# KUBODriver_Driver.net
KiCad netlist of a schematic drawn in Altium Designer
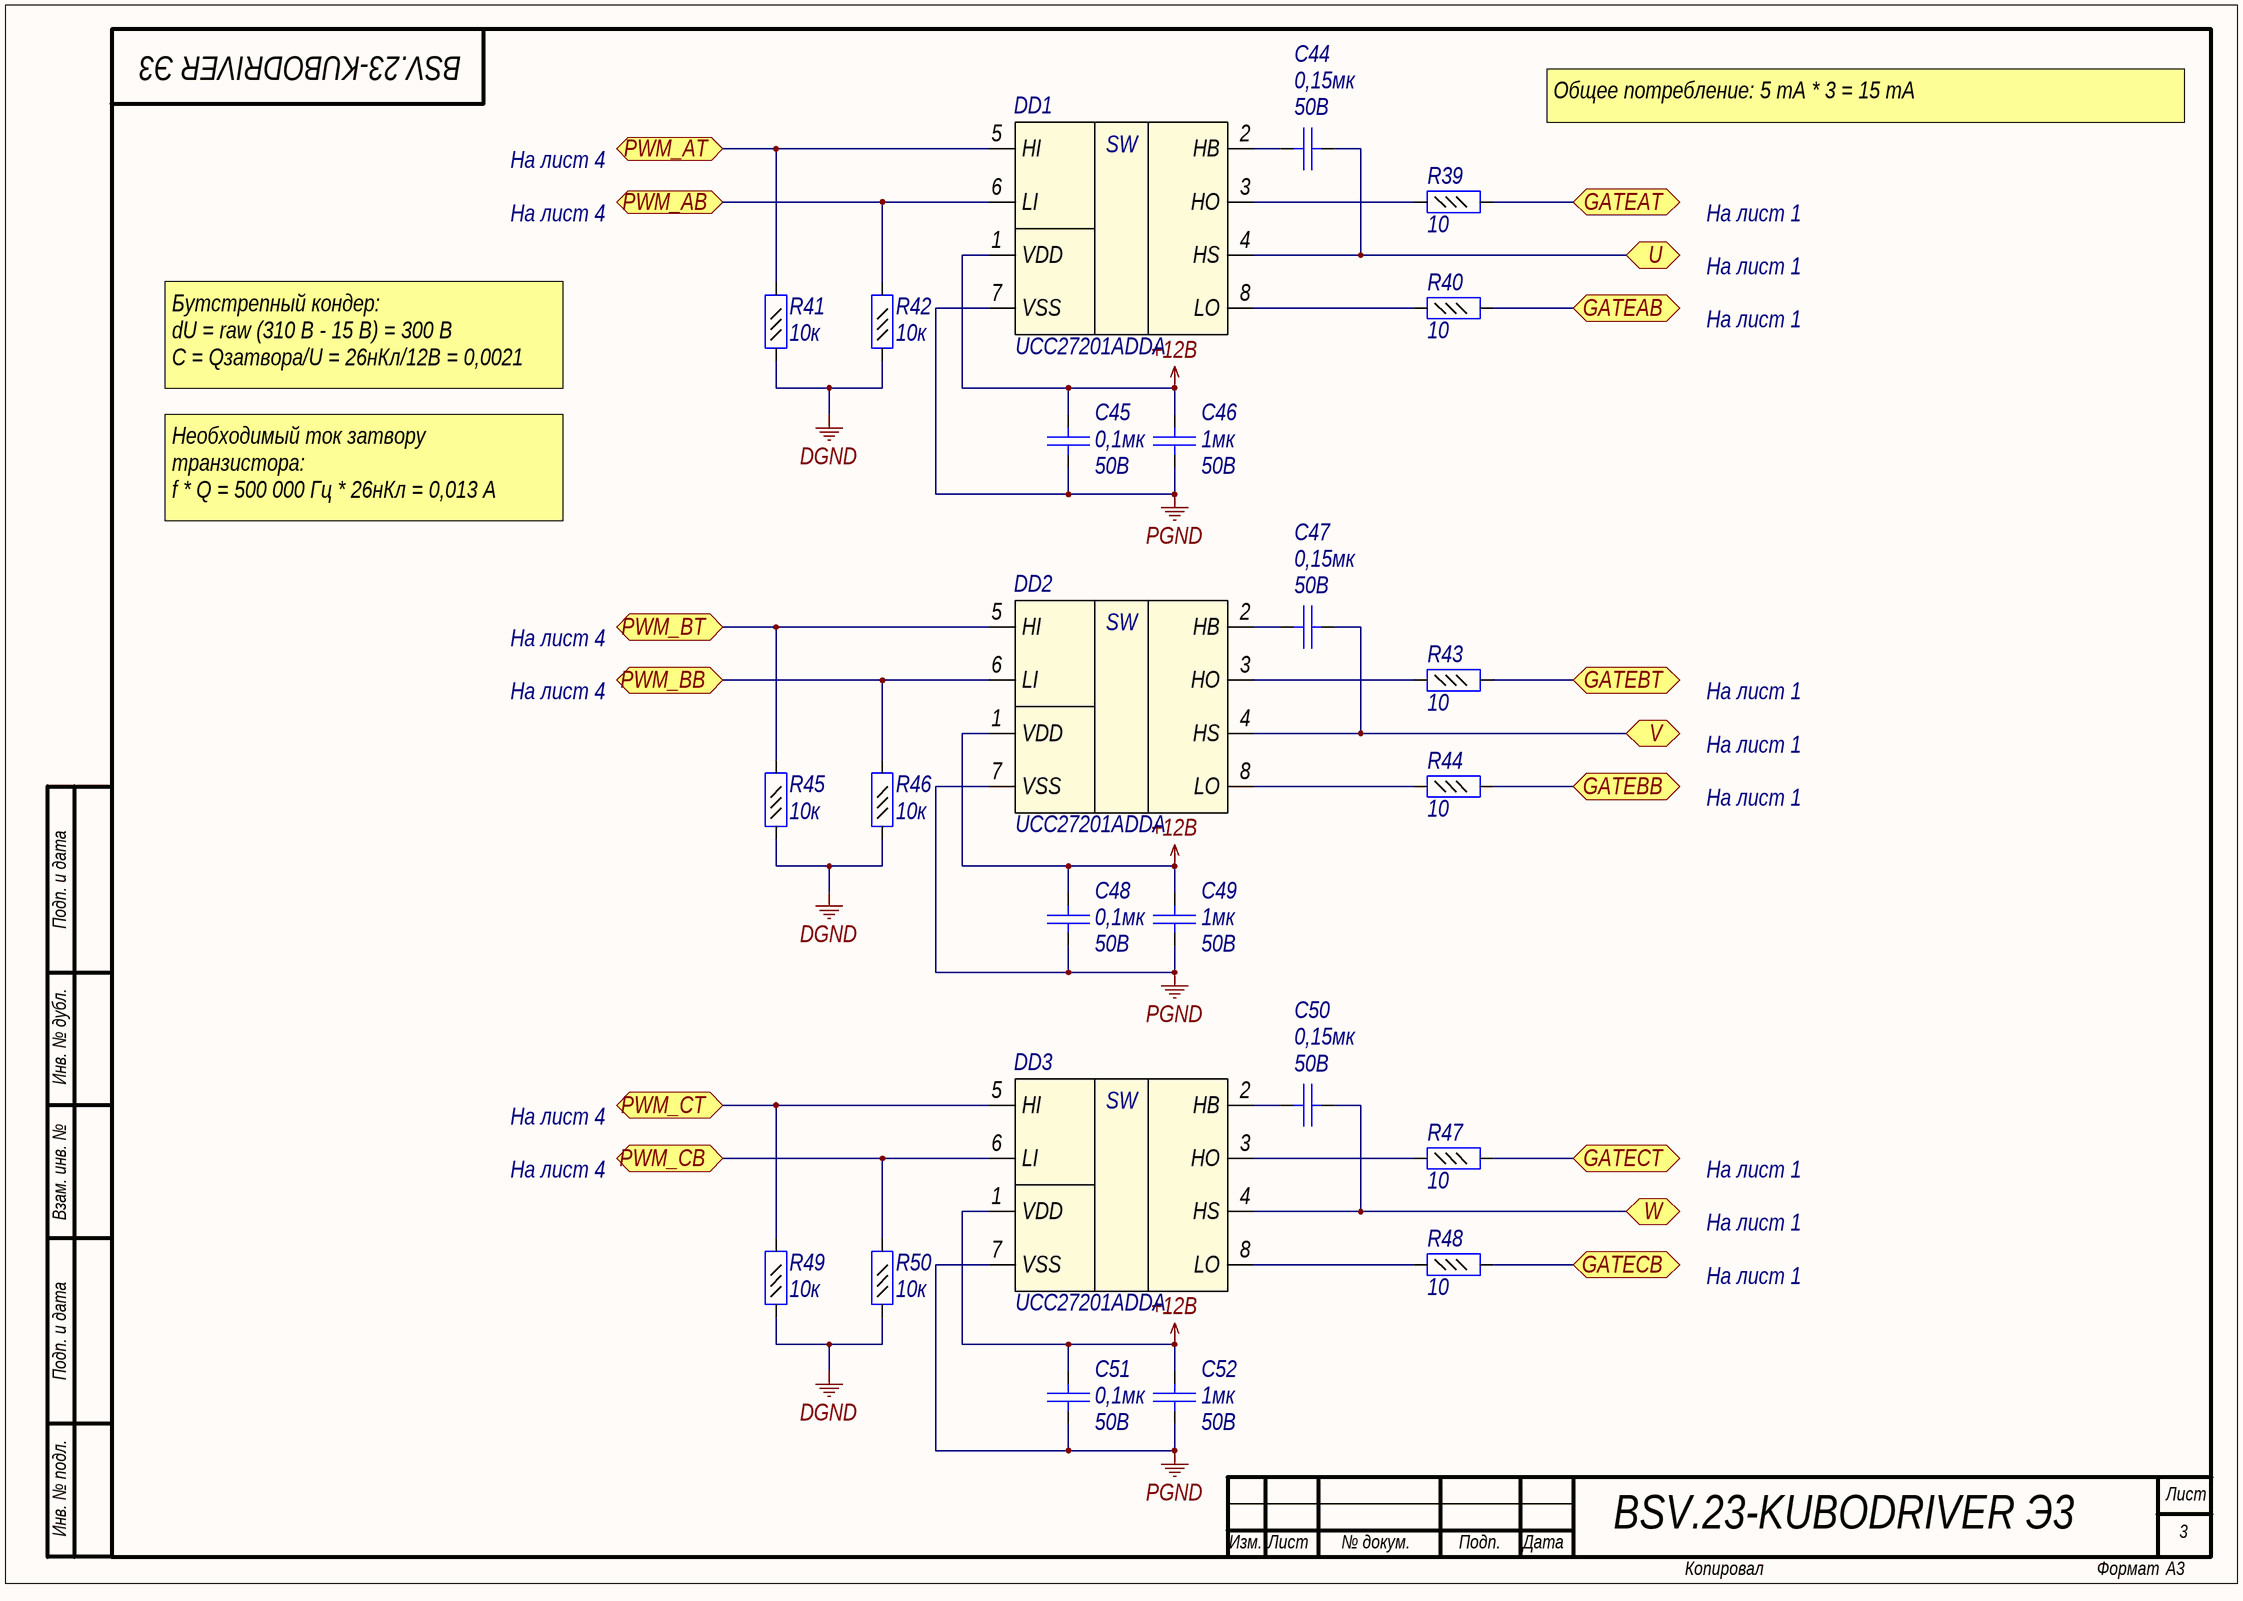
[diagram p0: KUBODriver_Driver.SchDoc]

(export (version "E")
  (design (tool "Eeschema 10.0.6"))
  (components
    (comp (ref "C44")
      (value "0,15мк")
      (footprint "C1812")
      (description "Конденсатор")
      (fields (field (name "VOLTAGE") "50В") (field (name "PART NUMBER") "C4532C0G1H154J250KA "))
      (libsource (lib "MOP44") (part "Capacitor"))
    )
    (comp (ref "C45")
      (value "0,1мк")
      (footprint "C0402")
      (description "Конденсатор")
      (fields
        (field (name "VOLTAGE") "50В")
        (field (name "PART NUMBER") "GRM155R71H104KE14D ")
        (field (name "Comment") "Capacitor")
      )
      (libsource (lib "MOP44") (part "Capacitor"))
    )
    (comp (ref "C46")
      (value "1мк")
      (footprint "C0805")
      (description "Конденсатор")
      (fields
        (field (name "VOLTAGE") "50B")
        (field (name "PART NUMBER") "GRM21BR71H105K")
        (field (name "Comment") "Capacitor")
      )
      (libsource (lib "MOP44") (part "Capacitor"))
    )
    (comp (ref "C47")
      (value "0,15мк")
      (footprint "C1812")
      (description "Конденсатор")
      (fields (field (name "VOLTAGE") "50В") (field (name "PART NUMBER") "C4532C0G1H154J250KA "))
      (libsource (lib "MOP44") (part "Capacitor"))
    )
    (comp (ref "C48")
      (value "0,1мк")
      (footprint "C0402")
      (description "Конденсатор")
      (fields
        (field (name "VOLTAGE") "50В")
        (field (name "PART NUMBER") "GRM155R71H104KE14D ")
        (field (name "Comment") "Capacitor")
      )
      (libsource (lib "MOP44") (part "Capacitor"))
    )
    (comp (ref "C49")
      (value "1мк")
      (footprint "C0805")
      (description "Конденсатор")
      (fields
        (field (name "VOLTAGE") "50B")
        (field (name "PART NUMBER") "GRM21BR71H105K")
        (field (name "Comment") "Capacitor")
      )
      (libsource (lib "MOP44") (part "Capacitor"))
    )
    (comp (ref "C50")
      (value "0,15мк")
      (footprint "C1812")
      (description "Конденсатор")
      (fields (field (name "VOLTAGE") "50В") (field (name "PART NUMBER") "C4532C0G1H154J250KA "))
      (libsource (lib "MOP44") (part "Capacitor"))
    )
    (comp (ref "C51")
      (value "0,1мк")
      (footprint "C0402")
      (description "Конденсатор")
      (fields
        (field (name "VOLTAGE") "50В")
        (field (name "PART NUMBER") "GRM155R71H104KE14D ")
        (field (name "Comment") "Capacitor")
      )
      (libsource (lib "MOP44") (part "Capacitor"))
    )
    (comp (ref "C52")
      (value "1мк")
      (footprint "C0805")
      (description "Конденсатор")
      (fields
        (field (name "VOLTAGE") "50B")
        (field (name "PART NUMBER") "GRM21BR71H105K")
        (field (name "Comment") "Capacitor")
      )
      (libsource (lib "MOP44") (part "Capacitor"))
    )
    (comp (ref "DD1")
      (value "UCC27201A")
      (footprint "HSOP8")
      (description "120-V Boot, 3-A Peak, High-Frequency, High-Side and Low-Side Driver")
      (fields (field (name "PART NUMBER") "UCC27201ADDA"))
      (libsource (lib "MOP44") (part "UCC27201A"))
    )
    (comp (ref "DD2")
      (value "UCC27201A")
      (footprint "HSOP8")
      (description "120-V Boot, 3-A Peak, High-Frequency, High-Side and Low-Side Driver")
      (fields (field (name "PART NUMBER") "UCC27201ADDA"))
      (libsource (lib "MOP44") (part "UCC27201A"))
    )
    (comp (ref "DD3")
      (value "UCC27201A")
      (footprint "HSOP8")
      (description "120-V Boot, 3-A Peak, High-Frequency, High-Side and Low-Side Driver")
      (fields (field (name "PART NUMBER") "UCC27201ADDA"))
      (libsource (lib "MOP44") (part "UCC27201A"))
    )
    (comp (ref "R39")
      (value "10")
      (footprint "R0402")
      (description "Резистор")
      (fields (field (name "PART NUMBER") "RC0402FR-0710RL") (field (name "POWER") "0,062Вт"))
      (libsource (lib "") (part "Resistor_0,062Вт_1"))
    )
    (comp (ref "R40")
      (value "10")
      (footprint "R0402")
      (description "Резистор")
      (fields (field (name "PART NUMBER") "RC0402FR-0710RL") (field (name "POWER") "0,062Вт"))
      (libsource (lib "") (part "Resistor_0,062Вт_1"))
    )
    (comp (ref "R41")
      (value "10к")
      (footprint "R0402")
      (description "Резистор")
      (fields (field (name "PART NUMBER") "RC0402FR-0710KL") (field (name "POWER") "0,062Вт"))
      (libsource (lib "MOP44") (part "Resistor_0,062Вт"))
    )
    (comp (ref "R42")
      (value "10к")
      (footprint "R0402")
      (description "Резистор")
      (fields (field (name "PART NUMBER") "RC0402FR-0710KL") (field (name "POWER") "0,062Вт"))
      (libsource (lib "MOP44") (part "Resistor_0,062Вт"))
    )
    (comp (ref "R43")
      (value "10")
      (footprint "R0402")
      (description "Резистор")
      (fields (field (name "PART NUMBER") "RC0402FR-0710RL") (field (name "POWER") "0,062Вт"))
      (libsource (lib "") (part "Resistor_0,062Вт_1"))
    )
    (comp (ref "R44")
      (value "10")
      (footprint "R0402")
      (description "Резистор")
      (fields (field (name "PART NUMBER") "RC0402FR-0710RL") (field (name "POWER") "0,062Вт"))
      (libsource (lib "") (part "Resistor_0,062Вт_1"))
    )
    (comp (ref "R45")
      (value "10к")
      (footprint "R0402")
      (description "Резистор")
      (fields (field (name "PART NUMBER") "RC0402FR-0710KL") (field (name "POWER") "0,062Вт"))
      (libsource (lib "MOP44") (part "Resistor_0,062Вт"))
    )
    (comp (ref "R46")
      (value "10к")
      (footprint "R0402")
      (description "Резистор")
      (fields (field (name "PART NUMBER") "RC0402FR-0710KL") (field (name "POWER") "0,062Вт"))
      (libsource (lib "MOP44") (part "Resistor_0,062Вт"))
    )
    (comp (ref "R47")
      (value "10")
      (footprint "R0402")
      (description "Резистор")
      (fields (field (name "PART NUMBER") "RC0402FR-0710RL") (field (name "POWER") "0,062Вт"))
      (libsource (lib "") (part "Resistor_0,062Вт_1"))
    )
    (comp (ref "R48")
      (value "10")
      (footprint "R0402")
      (description "Резистор")
      (fields (field (name "PART NUMBER") "RC0402FR-0710RL") (field (name "POWER") "0,062Вт"))
      (libsource (lib "") (part "Resistor_0,062Вт_1"))
    )
    (comp (ref "R49")
      (value "10к")
      (footprint "R0402")
      (description "Резистор")
      (fields (field (name "PART NUMBER") "RC0402FR-0710KL") (field (name "POWER") "0,062Вт"))
      (libsource (lib "MOP44") (part "Resistor_0,062Вт"))
    )
    (comp (ref "R50")
      (value "10к")
      (footprint "R0402")
      (description "Резистор")
      (fields (field (name "PART NUMBER") "RC0402FR-0710KL") (field (name "POWER") "0,062Вт"))
      (libsource (lib "MOP44") (part "Resistor_0,062Вт"))
    )
  )
  (nets
    (net (code "1") (name "+12B") (class "Default")
      (node (ref "C45") (pin "2") (pinfunction "2_2") (pintype "passive"))
      (node (ref "C46") (pin "2") (pinfunction "2_2") (pintype "passive"))
      (node (ref "C48") (pin "2") (pinfunction "2_2") (pintype "passive"))
      (node (ref "C49") (pin "2") (pinfunction "2_2") (pintype "passive"))
      (node (ref "C51") (pin "2") (pinfunction "2_2") (pintype "passive"))
      (node (ref "C52") (pin "2") (pinfunction "2_2") (pintype "passive"))
      (node (ref "DD1") (pin "1") (pinfunction "VDD_1") (pintype "passive"))
      (node (ref "DD2") (pin "1") (pinfunction "VDD_1") (pintype "passive"))
      (node (ref "DD3") (pin "1") (pinfunction "VDD_1") (pintype "passive"))
    )
    (net (code "2") (name "/GATEAB") (class "Default")
      (node (ref "R40") (pin "2") (pinfunction "2_2") (pintype "passive"))
    )
    (net (code "3") (name "/GATEAT") (class "Default")
      (node (ref "R39") (pin "2") (pinfunction "2_2") (pintype "passive"))
    )
    (net (code "4") (name "/GATEBB") (class "Default")
      (node (ref "R44") (pin "2") (pinfunction "2_2") (pintype "passive"))
    )
    (net (code "5") (name "/GATEBT") (class "Default")
      (node (ref "R43") (pin "2") (pinfunction "2_2") (pintype "passive"))
    )
    (net (code "6") (name "/GATECB") (class "Default")
      (node (ref "R48") (pin "2") (pinfunction "2_2") (pintype "passive"))
    )
    (net (code "7") (name "/GATECT") (class "Default")
      (node (ref "R47") (pin "2") (pinfunction "2_2") (pintype "passive"))
    )
    (net (code "8") (name "/PWM_AB") (class "Default")
      (node (ref "DD1") (pin "6") (pinfunction "LI_6") (pintype "passive"))
      (node (ref "R42") (pin "2") (pinfunction "2_2") (pintype "passive"))
    )
    (net (code "9") (name "/PWM_AT") (class "Default")
      (node (ref "DD1") (pin "5") (pinfunction "HI_5") (pintype "passive"))
      (node (ref "R41") (pin "2") (pinfunction "2_2") (pintype "passive"))
    )
    (net (code "10") (name "/PWM_BB") (class "Default")
      (node (ref "DD2") (pin "6") (pinfunction "LI_6") (pintype "passive"))
      (node (ref "R46") (pin "2") (pinfunction "2_2") (pintype "passive"))
    )
    (net (code "11") (name "/PWM_BT") (class "Default")
      (node (ref "DD2") (pin "5") (pinfunction "HI_5") (pintype "passive"))
      (node (ref "R45") (pin "2") (pinfunction "2_2") (pintype "passive"))
    )
    (net (code "12") (name "/PWM_CB") (class "Default")
      (node (ref "DD3") (pin "6") (pinfunction "LI_6") (pintype "passive"))
      (node (ref "R50") (pin "2") (pinfunction "2_2") (pintype "passive"))
    )
    (net (code "13") (name "/PWM_CT") (class "Default")
      (node (ref "DD3") (pin "5") (pinfunction "HI_5") (pintype "passive"))
      (node (ref "R49") (pin "2") (pinfunction "2_2") (pintype "passive"))
    )
    (net (code "14") (name "/U") (class "Default")
      (node (ref "C44") (pin "2") (pinfunction "2_2") (pintype "passive"))
      (node (ref "DD1") (pin "4") (pinfunction "HS_4") (pintype "passive"))
    )
    (net (code "15") (name "/V") (class "Default")
      (node (ref "C47") (pin "2") (pinfunction "2_2") (pintype "passive"))
      (node (ref "DD2") (pin "4") (pinfunction "HS_4") (pintype "passive"))
    )
    (net (code "16") (name "/W") (class "Default")
      (node (ref "C50") (pin "2") (pinfunction "2_2") (pintype "passive"))
      (node (ref "DD3") (pin "4") (pinfunction "HS_4") (pintype "passive"))
    )
    (net (code "17") (name "DGND") (class "Default")
      (node (ref "R41") (pin "1") (pinfunction "1_1") (pintype "passive"))
      (node (ref "R42") (pin "1") (pinfunction "1_1") (pintype "passive"))
      (node (ref "R45") (pin "1") (pinfunction "1_1") (pintype "passive"))
      (node (ref "R46") (pin "1") (pinfunction "1_1") (pintype "passive"))
      (node (ref "R49") (pin "1") (pinfunction "1_1") (pintype "passive"))
      (node (ref "R50") (pin "1") (pinfunction "1_1") (pintype "passive"))
    )
    (net (code "18") (name "Net-(DD1-HB)") (class "Default")
      (node (ref "C44") (pin "1") (pinfunction "1_1") (pintype "passive"))
      (node (ref "DD1") (pin "2") (pinfunction "HB_2") (pintype "passive"))
    )
    (net (code "19") (name "Net-(DD1-HO)") (class "Default")
      (node (ref "DD1") (pin "3") (pinfunction "HO_3") (pintype "passive"))
      (node (ref "R39") (pin "1") (pinfunction "1_1") (pintype "passive"))
    )
    (net (code "20") (name "Net-(DD1-LO)") (class "Default")
      (node (ref "DD1") (pin "8") (pinfunction "LO_8") (pintype "passive"))
      (node (ref "R40") (pin "1") (pinfunction "1_1") (pintype "passive"))
    )
    (net (code "21") (name "Net-(DD2-HB)") (class "Default")
      (node (ref "C47") (pin "1") (pinfunction "1_1") (pintype "passive"))
      (node (ref "DD2") (pin "2") (pinfunction "HB_2") (pintype "passive"))
    )
    (net (code "22") (name "Net-(DD2-HO)") (class "Default")
      (node (ref "DD2") (pin "3") (pinfunction "HO_3") (pintype "passive"))
      (node (ref "R43") (pin "1") (pinfunction "1_1") (pintype "passive"))
    )
    (net (code "23") (name "Net-(DD2-LO)") (class "Default")
      (node (ref "DD2") (pin "8") (pinfunction "LO_8") (pintype "passive"))
      (node (ref "R44") (pin "1") (pinfunction "1_1") (pintype "passive"))
    )
    (net (code "24") (name "Net-(DD3-HB)") (class "Default")
      (node (ref "C50") (pin "1") (pinfunction "1_1") (pintype "passive"))
      (node (ref "DD3") (pin "2") (pinfunction "HB_2") (pintype "passive"))
    )
    (net (code "25") (name "Net-(DD3-HO)") (class "Default")
      (node (ref "DD3") (pin "3") (pinfunction "HO_3") (pintype "passive"))
      (node (ref "R47") (pin "1") (pinfunction "1_1") (pintype "passive"))
    )
    (net (code "26") (name "Net-(DD3-LO)") (class "Default")
      (node (ref "DD3") (pin "8") (pinfunction "LO_8") (pintype "passive"))
      (node (ref "R48") (pin "1") (pinfunction "1_1") (pintype "passive"))
    )
    (net (code "27") (name "PGND") (class "Default")
      (node (ref "C45") (pin "1") (pinfunction "1_1") (pintype "passive"))
      (node (ref "C46") (pin "1") (pinfunction "1_1") (pintype "passive"))
      (node (ref "C48") (pin "1") (pinfunction "1_1") (pintype "passive"))
      (node (ref "C49") (pin "1") (pinfunction "1_1") (pintype "passive"))
      (node (ref "C51") (pin "1") (pinfunction "1_1") (pintype "passive"))
      (node (ref "C52") (pin "1") (pinfunction "1_1") (pintype "passive"))
      (node (ref "DD1") (pin "7") (pinfunction "VSS_7") (pintype "passive"))
      (node (ref "DD2") (pin "7") (pinfunction "VSS_7") (pintype "passive"))
      (node (ref "DD3") (pin "7") (pinfunction "VSS_7") (pintype "passive"))
    )
  )
)
